# doan20192.net
KiCad netlist of a schematic drawn in EasyEDA
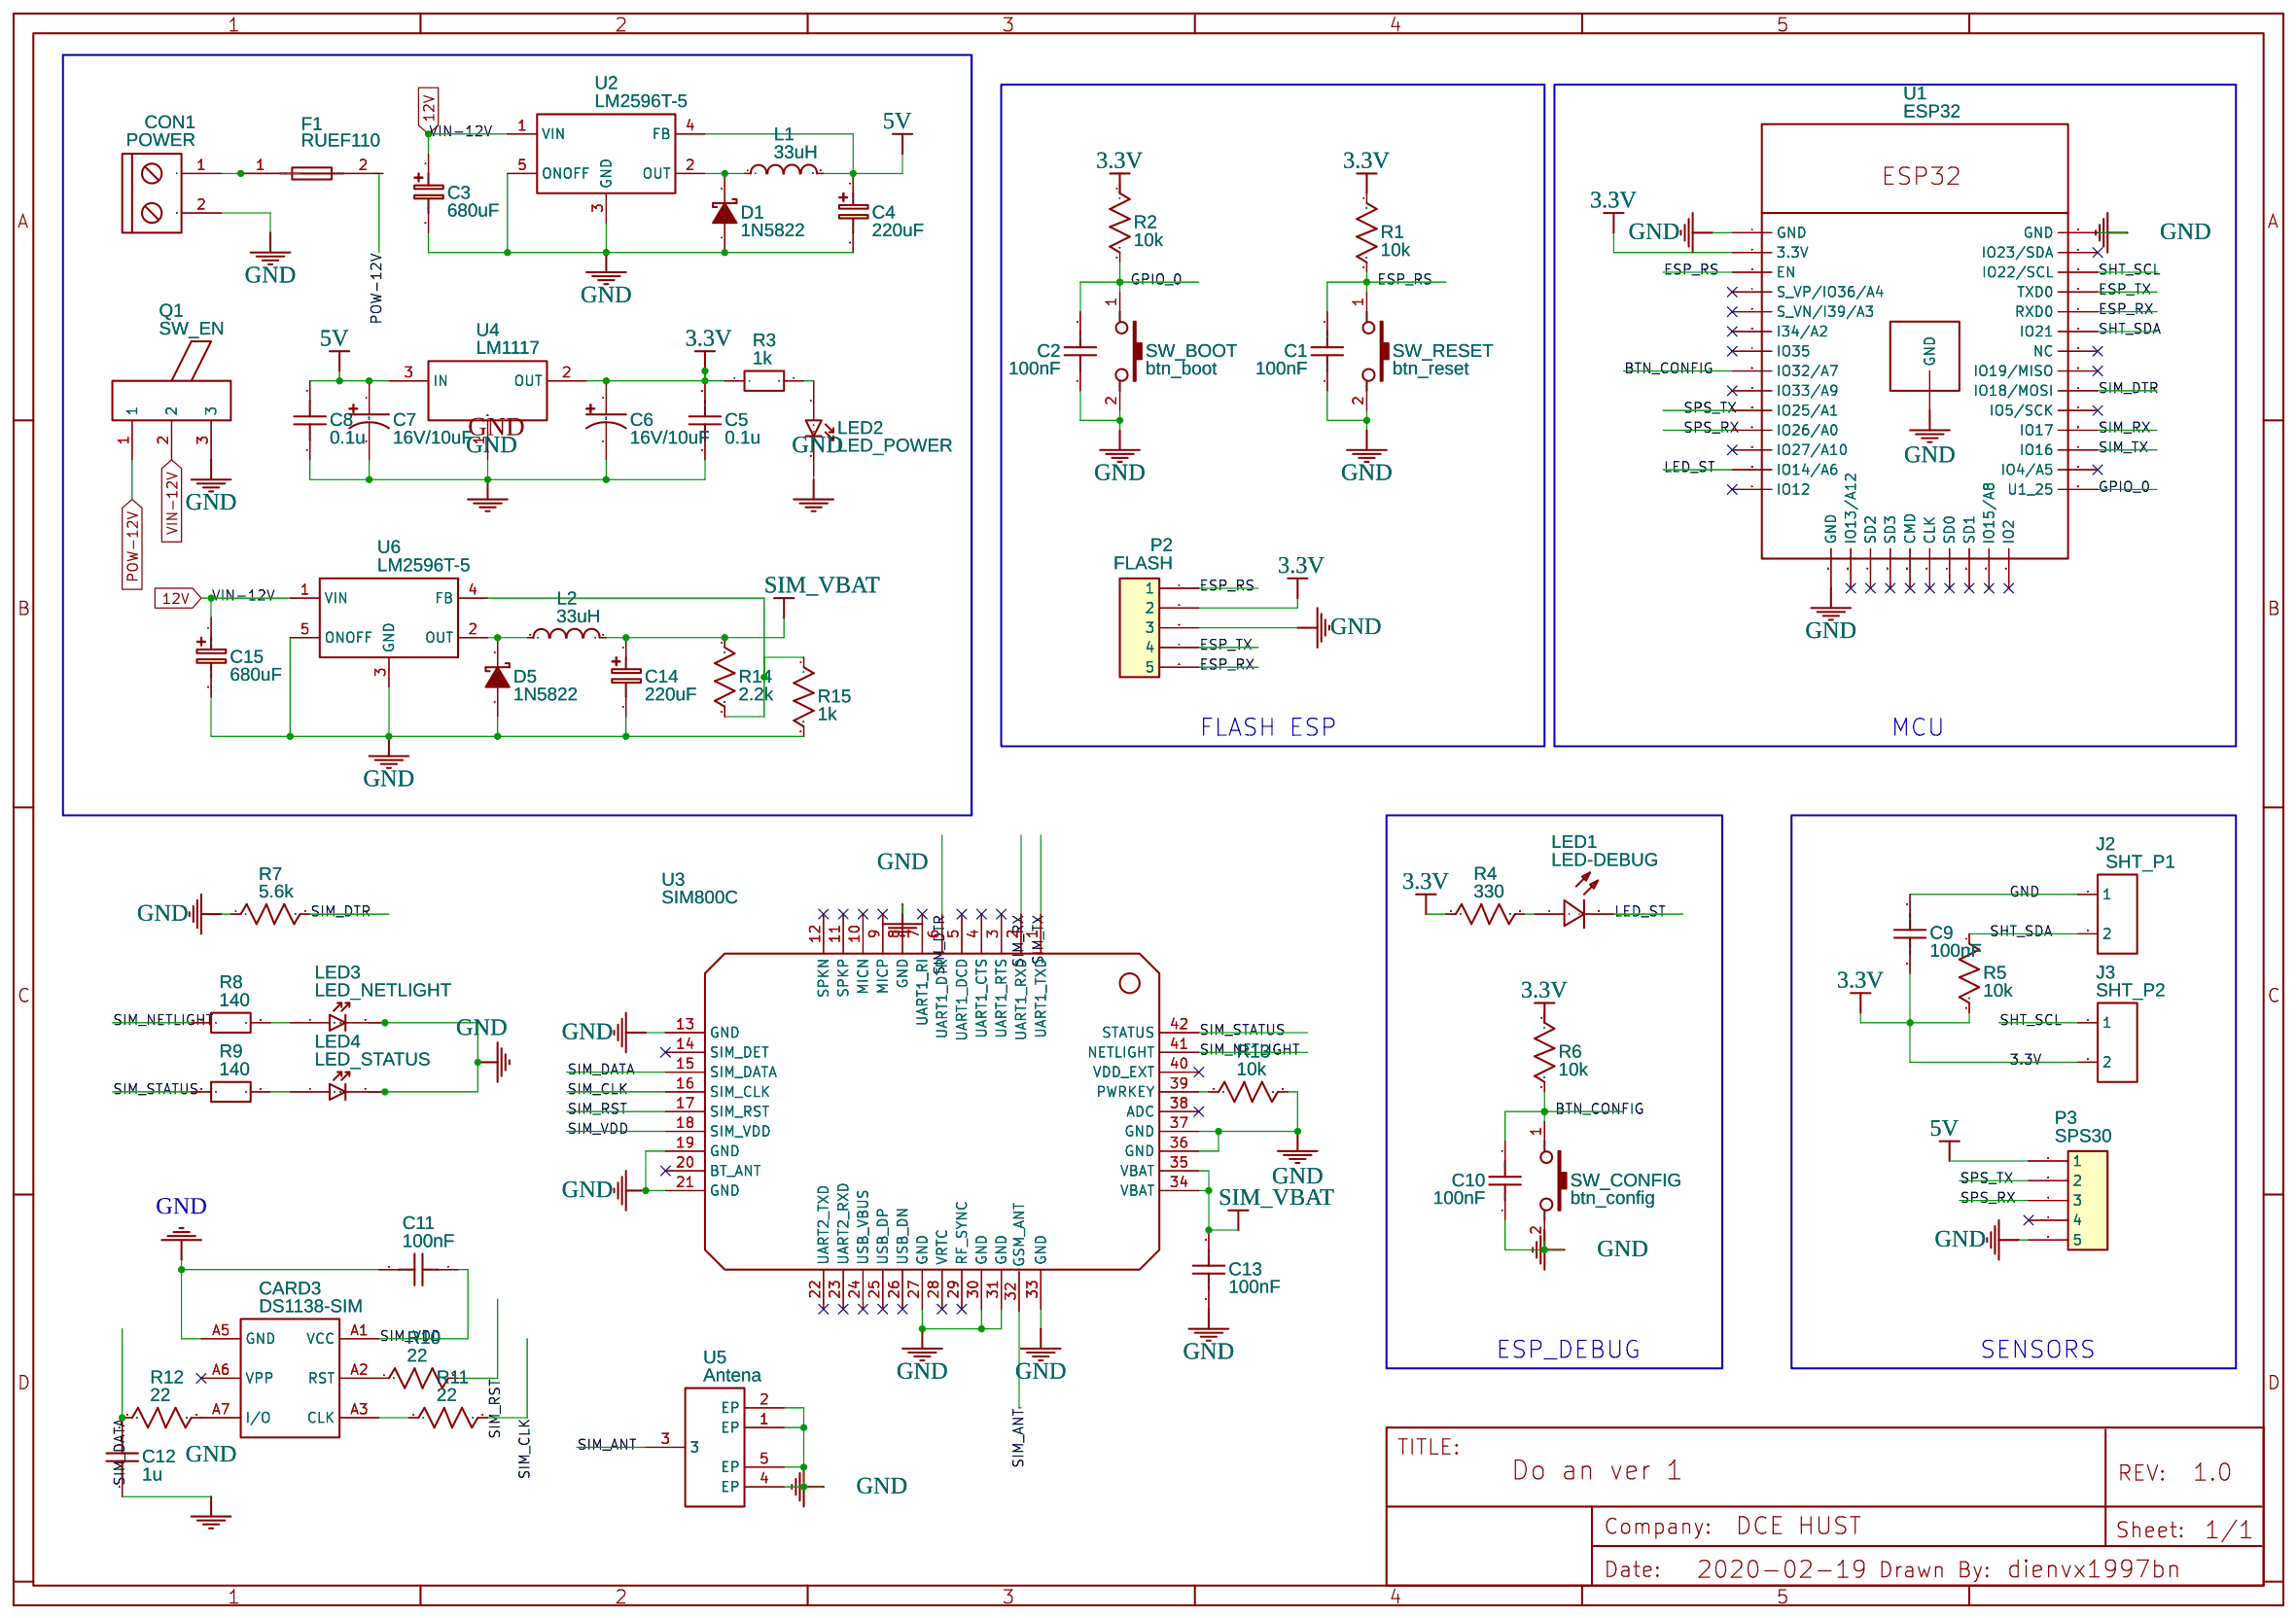
[diagram p0: schematic sheet]

(export (version "E")
  (design (tool "Eeschema 10.0.6"))
  (components
    (comp (ref "C1") (value "100nF") (libsource (lib "") (part "Cap_RAD-0.1_US")))
    (comp (ref "C2") (value "100nF") (libsource (lib "") (part "Cap_RAD-0.1_US")))
    (comp (ref "C3") (value "680uF") (libsource (lib "") (part "Cap_Electrolytic(TH)_D3.0XF1.5_EU_1")))
    (comp (ref "C4") (value "220uF") (libsource (lib "") (part "Cap_Electrolytic(TH)_D3.0XF1.5_EU")))
    (comp (ref "C5") (value "0.1u") (libsource (lib "") (part "Cap_RAD-0.1_US_1")))
    (comp (ref "C6") (value "16V/10uF") (libsource (lib "") (part "Cap_Electrolytic(TH)_D3.0XF1.5_US")))
    (comp (ref "C7") (value "16V/10uF") (libsource (lib "") (part "Cap_Electrolytic(TH)_D3.0XF1.5_US_1")))
    (comp (ref "C8") (value "0.1u") (libsource (lib "") (part "Cap_RAD-0.1_US_1")))
    (comp (ref "C9") (value "100nF") (libsource (lib "") (part "Cap_RAD-0.1_US_1")))
    (comp (ref "C10") (value "100nF") (libsource (lib "") (part "Cap_RAD-0.1_US")))
    (comp (ref "C11") (value "100nF") (libsource (lib "") (part "Cap_RAD-0.1_US_2")))
    (comp (ref "C12") (value "1u") (libsource (lib "") (part "Cap_RAD-0.1_US_1")))
    (comp (ref "C13") (value "100nF") (libsource (lib "") (part "Cap_RAD-0.1_US_1")))
    (comp (ref "C14") (value "220uF") (libsource (lib "") (part "Cap_Electrolytic(TH)_D3.0XF1.5_EU_3")))
    (comp (ref "C15") (value "680uF") (libsource (lib "") (part "Cap_Electrolytic(TH)_D3.0XF1.5_EU_2")))
    (comp (ref "CARD3")
      (value "DS1138-SIM")
      (fields
        (field (name "BOM_Manufacturer Part") "DS1138-06-06SS4BSR")
        (field (name "BOM_Supplier Part") "C96105")
      )
      (libsource (lib "") (part "Unknown_150_-110"))
    )
    (comp (ref "CON1")
      (value "POWER")
      (fields (field (name "BOM_Manufacturer Part") "Connector_2pin"))
      (libsource (lib "") (part "Connector_2pin"))
    )
    (comp (ref "D1")
      (value "1N5822")
      (fields (field (name "BOM_Supplier Part") "C82806"))
      (libsource (lib "") (part "1N5822"))
    )
    (comp (ref "D5")
      (value "1N5822")
      (fields (field (name "BOM_Supplier Part") "C82806"))
      (libsource (lib "") (part "1N5822"))
    )
    (comp (ref "F1")
      (value "RUEF110")
      (fields (field (name "BOM_Supplier Part") "C5395"))
      (libsource (lib "") (part "RUEF110"))
    )
    (comp (ref "J2")
      (value "SHT_P1")
      (fields (field (name "BOM_Manufacturer Part") "826629-2") (field (name "BOM_Supplier Part") "C86471"))
      (libsource (lib "") (part "J-Header-Male-2.54_1x2"))
    )
    (comp (ref "J3")
      (value "SHT_P2")
      (fields (field (name "BOM_Manufacturer Part") "826629-2") (field (name "BOM_Supplier Part") "C86471"))
      (libsource (lib "") (part "J-Header-Male-2.54_1x2"))
    )
    (comp (ref "L1") (value "33uH") (libsource (lib "") (part "Inductor_AXIAL-0.4_US")))
    (comp (ref "L2") (value "33uH") (libsource (lib "") (part "Inductor_AXIAL-0.4_US")))
    (comp (ref "LED1")
      (value "LED-DEBUG")
      (fields
        (field (name "BOM_Manufacturer Part") "204-10SURD/S530-A3")
        (field (name "BOM_Supplier Part") "C99772")
      )
      (libsource (lib "") (part "LED-3MM"))
    )
    (comp (ref "LED2")
      (value "LED_POWER")
      (fields (field (name "BOM_Manufacturer Part") "LED-3MM-RED"))
      (libsource (lib "") (part "LED-3MM-RED"))
    )
    (comp (ref "LED3")
      (value "LED_NETLIGHT")
      (fields (field (name "BOM_Manufacturer Part") "LED-3MM-RED"))
      (libsource (lib "") (part "LED-3MM-RED_1"))
    )
    (comp (ref "LED4")
      (value "LED_STATUS")
      (fields (field (name "BOM_Manufacturer Part") "LED-3MM-RED"))
      (libsource (lib "") (part "LED-3MM-RED_1"))
    )
    (comp (ref "P2")
      (value "FLASH")
      (fields
        (field (name "BOM_Manufacturer Part") "Female header　2.54 1*5Ｐ")
        (field (name "BOM_Supplier Part") "C46341")
      )
      (libsource (lib "") (part "Header-Female-2.54_1x5"))
    )
    (comp (ref "P3")
      (value "SPS30")
      (fields
        (field (name "BOM_Manufacturer Part") "Female header　2.54 1*5Ｐ")
        (field (name "BOM_Supplier Part") "C46341")
      )
      (libsource (lib "") (part "Header-Female-2.54_1x5_1"))
    )
    (comp (ref "Q1")
      (value "SW_EN")
      (fields (field (name "BOM_Manufacturer Part") "MTS-103-A2"))
      (libsource (lib "") (part "MTS-103-A2"))
    )
    (comp (ref "R1") (value "10k") (libsource (lib "") (part "Res_AXIAL-0.3(1/8W)_US")))
    (comp (ref "R2") (value "10k") (libsource (lib "") (part "Res_AXIAL-0.3(1/8W)_US")))
    (comp (ref "R3") (value "1k") (libsource (lib "") (part "Res_AXIAL-0.3(1/8W)_EU")))
    (comp (ref "R4") (value "330") (libsource (lib "") (part "Res_AXIAL-0.3(1/8W)_US_1")))
    (comp (ref "R5") (value "10k") (libsource (lib "") (part "Res_AXIAL-0.3(1/8W)_US")))
    (comp (ref "R6") (value "10k") (libsource (lib "") (part "Res_AXIAL-0.3(1/8W)_US")))
    (comp (ref "R7") (value "5.6k") (libsource (lib "") (part "Res_AXIAL-0.3(1/8W)_US_1")))
    (comp (ref "R8") (value "140") (libsource (lib "") (part "Res_AXIAL-0.3(1/8W)_EU")))
    (comp (ref "R9") (value "140") (libsource (lib "") (part "Res_AXIAL-0.3(1/8W)_EU")))
    (comp (ref "R10") (value "22") (libsource (lib "") (part "Res_AXIAL-0.3(1/8W)_US_1")))
    (comp (ref "R11") (value "22") (libsource (lib "") (part "Res_AXIAL-0.3(1/8W)_US_1")))
    (comp (ref "R12") (value "22") (libsource (lib "") (part "Res_AXIAL-0.3(1/8W)_US_1")))
    (comp (ref "R13") (value "10k") (libsource (lib "") (part "Res_AXIAL-0.3(1/8W)_US_1")))
    (comp (ref "R14") (value "2.2k") (libsource (lib "") (part "Res_AXIAL-0.3(1/8W)_US")))
    (comp (ref "R15") (value "1k") (libsource (lib "") (part "Res_AXIAL-0.3(1/8W)_US")))
    (comp (ref "SW_BOOT")
      (value "btn_boot")
      (fields
        (field (name "BOM_Manufacturer Part") "Switch,6*6*6Plastic head,260G, 0.25mm,Straight line")
        (field (name "BOM_Supplier Part") "C71836")
      )
      (libsource (lib "") (part "Button-6x6x6mm"))
    )
    (comp (ref "SW_CONFIG")
      (value "btn_config")
      (fields
        (field (name "BOM_Manufacturer Part") "Switch,6*6*6Plastic head,260G, 0.25mm,Straight line")
        (field (name "BOM_Supplier Part") "C71836")
      )
      (libsource (lib "") (part "Button-6x6x6mm_2"))
    )
    (comp (ref "SW_RESET")
      (value "btn_reset")
      (fields
        (field (name "BOM_Manufacturer Part") "Switch,6*6*6Plastic head,260G, 0.25mm,Straight line")
        (field (name "BOM_Supplier Part") "C71836")
      )
      (libsource (lib "") (part "Button-6x6x6mm_1"))
    )
    (comp (ref "U1")
      (value "ESP32")
      (fields (field (name "BOM_Manufacturer Part") "New SchematicLib"))
      (libsource (lib "") (part "ESP32"))
    )
    (comp (ref "U2")
      (value "LM2596T-5")
      (fields (field (name "BOM_Supplier Part") "undefined"))
      (libsource (lib "") (part "LM2596T-5"))
    )
    (comp (ref "U3")
      (value "SIM800C")
      (fields
        (field (name "BOM_Manufacturer Part") "SIM800C 24Mbit")
        (field (name "BOM_Supplier Part") "C69119")
      )
      (libsource (lib "") (part "SIM800C"))
    )
    (comp (ref "U4") (value "LM1117") (libsource (lib "") (part "LM1117T-5.0NOPB")))
    (comp (ref "U5")
      (value "Antena")
      (fields
        (field (name "BOM_Manufacturer Part") "5-1814832-1")
        (field (name "BOM_Supplier Part") "C127838")
      )
      (libsource (lib "") (part "Unknown_360_-85"))
    )
    (comp (ref "U6")
      (value "LM2596T-5")
      (fields (field (name "BOM_Supplier Part") "undefined"))
      (libsource (lib "") (part "LM2596T-5"))
    )
  )
  (nets
    (net (code "1") (name "/BTN_CONFIG") (class "Default")
      (node (ref "C10") (pin "2") (pinfunction "2_2") (pintype "unspecified"))
      (node (ref "R6") (pin "2") (pinfunction "2_2") (pintype "unspecified"))
      (node (ref "SW_CONFIG") (pin "1") (pinfunction "1_1") (pintype "input"))
      (node (ref "U1") (pin "8") (pinfunction "IO32/A7_8") (pintype "unspecified"))
    )
    (net (code "2") (name "/ESP_RS") (class "Default")
      (node (ref "C1") (pin "2") (pinfunction "2_2") (pintype "unspecified"))
      (node (ref "P2") (pin "1") (pinfunction "1_1") (pintype "input"))
      (node (ref "R1") (pin "2") (pinfunction "2_2") (pintype "unspecified"))
      (node (ref "SW_RESET") (pin "1") (pinfunction "1_1") (pintype "input"))
      (node (ref "U1") (pin "3") (pinfunction "EN_3") (pintype "unspecified"))
    )
    (net (code "3") (name "/ESP_RX") (class "Default")
      (node (ref "P2") (pin "5") (pinfunction "5_5") (pintype "input"))
      (node (ref "U1") (pin "34") (pinfunction "RXD0_34") (pintype "unspecified"))
    )
    (net (code "4") (name "/ESP_TX") (class "Default")
      (node (ref "P2") (pin "4") (pinfunction "4_4") (pintype "input"))
      (node (ref "U1") (pin "35") (pinfunction "TXD0_35") (pintype "unspecified"))
    )
    (net (code "5") (name "/GPIO_0") (class "Default")
      (node (ref "C2") (pin "2") (pinfunction "2_2") (pintype "unspecified"))
      (node (ref "R2") (pin "2") (pinfunction "2_2") (pintype "unspecified"))
      (node (ref "SW_BOOT") (pin "1") (pinfunction "1_1") (pintype "input"))
      (node (ref "U1") (pin "25") (pinfunction "U1_25_25") (pintype "unspecified"))
    )
    (net (code "6") (name "/LED_ST") (class "Default")
      (node (ref "LED1") (pin "2") (pinfunction "-_2") (pintype "unspecified"))
      (node (ref "U1") (pin "13") (pinfunction "IO14/A6_13") (pintype "unspecified"))
    )
    (net (code "7") (name "/SHT_SCL") (class "Default")
      (node (ref "J3") (pin "1") (pinfunction "1_1") (pintype "unspecified"))
      (node (ref "U1") (pin "36") (pinfunction "IO22/SCL_36") (pintype "unspecified"))
    )
    (net (code "8") (name "/SHT_SDA") (class "Default")
      (node (ref "J2") (pin "2") (pinfunction "2_2") (pintype "unspecified"))
      (node (ref "R5") (pin "1") (pinfunction "1_1") (pintype "unspecified"))
      (node (ref "U1") (pin "33") (pinfunction "IO21_33") (pintype "unspecified"))
    )
    (net (code "9") (name "/SIM_ANT") (class "Default")
      (node (ref "U3") (pin "32") (pinfunction "GSM_ANT_32") (pintype "unspecified"))
      (node (ref "U5") (pin "3") (pinfunction "3_3") (pintype "unspecified"))
    )
    (net (code "10") (name "/SIM_CLK") (class "Default")
      (node (ref "R11") (pin "2") (pinfunction "2_2") (pintype "unspecified"))
      (node (ref "U3") (pin "16") (pinfunction "SIM_CLK_16") (pintype "unspecified"))
    )
    (net (code "11") (name "/SIM_DATA") (class "Default")
      (node (ref "C12") (pin "2") (pinfunction "2_2") (pintype "unspecified"))
      (node (ref "R12") (pin "1") (pinfunction "1_1") (pintype "unspecified"))
      (node (ref "U3") (pin "15") (pinfunction "SIM_DATA_15") (pintype "unspecified"))
    )
    (net (code "12") (name "/SIM_DTR") (class "Default")
      (node (ref "R7") (pin "2") (pinfunction "2_2") (pintype "unspecified"))
      (node (ref "U1") (pin "30") (pinfunction "IO18/MOSI_30") (pintype "unspecified"))
      (node (ref "U3") (pin "6") (pinfunction "UART1_DTR_6") (pintype "unspecified"))
    )
    (net (code "13") (name "/SIM_NETLIGHT") (class "Default")
      (node (ref "R8") (pin "1") (pinfunction "1_1") (pintype "unspecified"))
      (node (ref "U3") (pin "41") (pinfunction "NETLIGHT_41") (pintype "unspecified"))
    )
    (net (code "14") (name "/SIM_RST") (class "Default")
      (node (ref "R10") (pin "2") (pinfunction "2_2") (pintype "unspecified"))
      (node (ref "U3") (pin "17") (pinfunction "SIM_RST_17") (pintype "unspecified"))
    )
    (net (code "15") (name "/SIM_RX") (class "Default")
      (node (ref "U1") (pin "28") (pinfunction "IO17_28") (pintype "unspecified"))
      (node (ref "U3") (pin "2") (pinfunction "UART1_RXD_2") (pintype "unspecified"))
    )
    (net (code "16") (name "/SIM_STATUS") (class "Default")
      (node (ref "R9") (pin "1") (pinfunction "1_1") (pintype "unspecified"))
      (node (ref "U3") (pin "42") (pinfunction "STATUS_42") (pintype "unspecified"))
    )
    (net (code "17") (name "/SIM_TX") (class "Default")
      (node (ref "U1") (pin "27") (pinfunction "IO16_27") (pintype "unspecified"))
      (node (ref "U3") (pin "1") (pinfunction "UART1_TXD_1") (pintype "unspecified"))
    )
    (net (code "18") (name "/SIM_VDD") (class "Default")
      (node (ref "C11") (pin "1") (pinfunction "1_1") (pintype "unspecified"))
      (node (ref "CARD3") (pin "A1") (pinfunction "VCC_A1") (pintype "unspecified"))
      (node (ref "U3") (pin "18") (pinfunction "SIM_VDD_18") (pintype "unspecified"))
    )
    (net (code "19") (name "/SPS_RX") (class "Default")
      (node (ref "P3") (pin "3") (pinfunction "3_3") (pintype "input"))
      (node (ref "U1") (pin "11") (pinfunction "IO26/A0_11") (pintype "unspecified"))
    )
    (net (code "20") (name "/SPS_TX") (class "Default")
      (node (ref "P3") (pin "2") (pinfunction "2_2") (pintype "input"))
      (node (ref "U1") (pin "10") (pinfunction "IO25/A1_10") (pintype "unspecified"))
    )
    (net (code "21") (name "3.3V") (class "Default")
      (node (ref "C5") (pin "2") (pinfunction "2_2") (pintype "unspecified"))
      (node (ref "C6") (pin "1") (pinfunction "1_1") (pintype "unspecified"))
      (node (ref "C9") (pin "1") (pinfunction "1_1") (pintype "unspecified"))
      (node (ref "J3") (pin "2") (pinfunction "2_2") (pintype "unspecified"))
      (node (ref "P2") (pin "2") (pinfunction "2_2") (pintype "input"))
      (node (ref "R1") (pin "1") (pinfunction "1_1") (pintype "unspecified"))
      (node (ref "R2") (pin "1") (pinfunction "1_1") (pintype "unspecified"))
      (node (ref "R3") (pin "1") (pinfunction "1_1") (pintype "unspecified"))
      (node (ref "R4") (pin "1") (pinfunction "1_1") (pintype "unspecified"))
      (node (ref "R5") (pin "2") (pinfunction "2_2") (pintype "unspecified"))
      (node (ref "R6") (pin "1") (pinfunction "1_1") (pintype "unspecified"))
      (node (ref "U1") (pin "2") (pinfunction "3.3V_2") (pintype "unspecified"))
      (node (ref "U4") (pin "2") (pinfunction "OUT_2") (pintype "passive"))
    )
    (net (code "22") (name "5V") (class "Default")
      (node (ref "C4") (pin "1") (pinfunction "1_1") (pintype "unspecified"))
      (node (ref "C7") (pin "1") (pinfunction "1_1") (pintype "unspecified"))
      (node (ref "C8") (pin "2") (pinfunction "2_2") (pintype "unspecified"))
      (node (ref "L1") (pin "2") (pinfunction "2_2") (pintype "unspecified"))
      (node (ref "P3") (pin "1") (pinfunction "1_1") (pintype "input"))
      (node (ref "U2") (pin "4") (pinfunction "FB_4") (pintype "input"))
      (node (ref "U4") (pin "3") (pinfunction "IN_3") (pintype "passive"))
    )
    (net (code "23") (name "12V") (class "Default")
      (node (ref "C15") (pin "1") (pinfunction "1_1") (pintype "unspecified"))
      (node (ref "C3") (pin "1") (pinfunction "1_1") (pintype "unspecified"))
      (node (ref "Q1") (pin "2") (pinfunction "2_2") (pintype "unspecified"))
      (node (ref "U2") (pin "1") (pinfunction "VIN_1") (pintype "passive"))
      (node (ref "U6") (pin "1") (pinfunction "VIN_1") (pintype "passive"))
    )
    (net (code "24") (name "GND") (class "Default")
      (node (ref "C1") (pin "1") (pinfunction "1_1") (pintype "unspecified"))
      (node (ref "C10") (pin "1") (pinfunction "1_1") (pintype "unspecified"))
      (node (ref "C11") (pin "2") (pinfunction "2_2") (pintype "unspecified"))
      (node (ref "C12") (pin "1") (pinfunction "1_1") (pintype "unspecified"))
      (node (ref "C13") (pin "1") (pinfunction "1_1") (pintype "unspecified"))
      (node (ref "C14") (pin "2") (pinfunction "2_2") (pintype "unspecified"))
      (node (ref "C15") (pin "2") (pinfunction "2_2") (pintype "unspecified"))
      (node (ref "C2") (pin "1") (pinfunction "1_1") (pintype "unspecified"))
      (node (ref "C3") (pin "2") (pinfunction "2_2") (pintype "unspecified"))
      (node (ref "C4") (pin "2") (pinfunction "2_2") (pintype "unspecified"))
      (node (ref "C5") (pin "1") (pinfunction "1_1") (pintype "unspecified"))
      (node (ref "C6") (pin "2") (pinfunction "2_2") (pintype "unspecified"))
      (node (ref "C7") (pin "2") (pinfunction "2_2") (pintype "unspecified"))
      (node (ref "C8") (pin "1") (pinfunction "1_1") (pintype "unspecified"))
      (node (ref "C9") (pin "2") (pinfunction "2_2") (pintype "unspecified"))
      (node (ref "CARD3") (pin "A5") (pinfunction "GND_A5") (pintype "unspecified"))
      (node (ref "CON1") (pin "2") (pinfunction "2_2") (pintype "unspecified"))
      (node (ref "D1") (pin "1") (pinfunction "A_1") (pintype "unspecified"))
      (node (ref "D5") (pin "1") (pinfunction "A_1") (pintype "unspecified"))
      (node (ref "J2") (pin "1") (pinfunction "1_1") (pintype "unspecified"))
      (node (ref "LED2") (pin "2") (pinfunction "2_2") (pintype "unspecified"))
      (node (ref "LED3") (pin "2") (pinfunction "2_2") (pintype "unspecified"))
      (node (ref "LED4") (pin "2") (pinfunction "2_2") (pintype "unspecified"))
      (node (ref "P2") (pin "3") (pinfunction "3_3") (pintype "input"))
      (node (ref "P3") (pin "5") (pinfunction "5_5") (pintype "input"))
      (node (ref "Q1") (pin "3") (pinfunction "3_3") (pintype "unspecified"))
      (node (ref "R13") (pin "2") (pinfunction "2_2") (pintype "unspecified"))
      (node (ref "R15") (pin "2") (pinfunction "2_2") (pintype "unspecified"))
      (node (ref "R7") (pin "1") (pinfunction "1_1") (pintype "unspecified"))
      (node (ref "SW_BOOT") (pin "2") (pinfunction "2_2") (pintype "input"))
      (node (ref "SW_CONFIG") (pin "2") (pinfunction "2_2") (pintype "input"))
      (node (ref "SW_RESET") (pin "2") (pinfunction "2_2") (pintype "input"))
      (node (ref "U1") (pin "1") (pinfunction "GND_1") (pintype "unspecified"))
      (node (ref "U1") (pin "15") (pinfunction "GND_15") (pintype "unspecified"))
      (node (ref "U1") (pin "38") (pinfunction "GND_38") (pintype "unspecified"))
      (node (ref "U1") (pin "39") (pinfunction "GND_39") (pintype "unspecified"))
      (node (ref "U2") (pin "3") (pinfunction "GND_3") (pintype "passive"))
      (node (ref "U2") (pin "5") (pinfunction "ONOFF_5") (pintype "input"))
      (node (ref "U3") (pin "13") (pinfunction "GND_13") (pintype "unspecified"))
      (node (ref "U3") (pin "19") (pinfunction "GND_19") (pintype "unspecified"))
      (node (ref "U3") (pin "21") (pinfunction "GND_21") (pintype "unspecified"))
      (node (ref "U3") (pin "27") (pinfunction "GND_27") (pintype "unspecified"))
      (node (ref "U3") (pin "30") (pinfunction "GND_30") (pintype "unspecified"))
      (node (ref "U3") (pin "31") (pinfunction "GND_31") (pintype "unspecified"))
      (node (ref "U3") (pin "33") (pinfunction "GND_33") (pintype "unspecified"))
      (node (ref "U3") (pin "36") (pinfunction "GND_36") (pintype "unspecified"))
      (node (ref "U3") (pin "37") (pinfunction "GND_37") (pintype "unspecified"))
      (node (ref "U3") (pin "8") (pinfunction "GND_8") (pintype "unspecified"))
      (node (ref "U4") (pin "1") (pinfunction "GND_1") (pintype "passive"))
      (node (ref "U5") (pin "1") (pinfunction "EP_1") (pintype "unspecified"))
      (node (ref "U5") (pin "2") (pinfunction "EP_2") (pintype "unspecified"))
      (node (ref "U5") (pin "4") (pinfunction "EP_4") (pintype "unspecified"))
      (node (ref "U5") (pin "5") (pinfunction "EP_5") (pintype "unspecified"))
      (node (ref "U6") (pin "3") (pinfunction "GND_3") (pintype "passive"))
      (node (ref "U6") (pin "5") (pinfunction "ONOFF_5") (pintype "input"))
    )
    (net (code "25") (name "Net-(CARD3-CLK)") (class "Default")
      (node (ref "CARD3") (pin "A3") (pinfunction "CLK_A3") (pintype "unspecified"))
      (node (ref "R11") (pin "1") (pinfunction "1_1") (pintype "unspecified"))
    )
    (net (code "26") (name "Net-(CARD3-I{slash}O)") (class "Default")
      (node (ref "CARD3") (pin "A7") (pinfunction "I/O_A7") (pintype "unspecified"))
      (node (ref "R12") (pin "2") (pinfunction "2_2") (pintype "unspecified"))
    )
    (net (code "27") (name "Net-(CARD3-RST)") (class "Default")
      (node (ref "CARD3") (pin "A2") (pinfunction "RST_A2") (pintype "unspecified"))
      (node (ref "R10") (pin "1") (pinfunction "1_1") (pintype "unspecified"))
    )
    (net (code "28") (name "Net-(CON1-Pad1)") (class "Default")
      (node (ref "CON1") (pin "1") (pinfunction "1_1") (pintype "unspecified"))
      (node (ref "F1") (pin "1") (pinfunction "1_1") (pintype "unspecified"))
    )
    (net (code "29") (name "Net-(D1-K)") (class "Default")
      (node (ref "D1") (pin "2") (pinfunction "K_2") (pintype "unspecified"))
      (node (ref "L1") (pin "1") (pinfunction "1_1") (pintype "unspecified"))
      (node (ref "U2") (pin "2") (pinfunction "OUT_2") (pintype "output"))
    )
    (net (code "30") (name "Net-(D5-K)") (class "Default")
      (node (ref "D5") (pin "2") (pinfunction "K_2") (pintype "unspecified"))
      (node (ref "L2") (pin "1") (pinfunction "1_1") (pintype "unspecified"))
      (node (ref "U6") (pin "2") (pinfunction "OUT_2") (pintype "output"))
    )
    (net (code "31") (name "Net-(LED1-+)") (class "Default")
      (node (ref "LED1") (pin "1") (pinfunction "+_1") (pintype "unspecified"))
      (node (ref "R4") (pin "2") (pinfunction "2_2") (pintype "unspecified"))
    )
    (net (code "32") (name "Net-(LED2-Pad1)") (class "Default")
      (node (ref "LED2") (pin "1") (pinfunction "1_1") (pintype "unspecified"))
      (node (ref "R3") (pin "2") (pinfunction "2_2") (pintype "unspecified"))
    )
    (net (code "33") (name "Net-(LED3-Pad1)") (class "Default")
      (node (ref "LED3") (pin "1") (pinfunction "1_1") (pintype "unspecified"))
      (node (ref "R8") (pin "2") (pinfunction "2_2") (pintype "unspecified"))
    )
    (net (code "34") (name "Net-(LED4-Pad1)") (class "Default")
      (node (ref "LED4") (pin "1") (pinfunction "1_1") (pintype "unspecified"))
      (node (ref "R9") (pin "2") (pinfunction "2_2") (pintype "unspecified"))
    )
    (net (code "35") (name "Net-(U3-PWRKEY)") (class "Default")
      (node (ref "R13") (pin "1") (pinfunction "1_1") (pintype "unspecified"))
      (node (ref "U3") (pin "39") (pinfunction "PWRKEY_39") (pintype "unspecified"))
    )
    (net (code "36") (name "Net-(U6-FB)") (class "Default")
      (node (ref "R14") (pin "2") (pinfunction "2_2") (pintype "unspecified"))
      (node (ref "R15") (pin "1") (pinfunction "1_1") (pintype "unspecified"))
      (node (ref "U6") (pin "4") (pinfunction "FB_4") (pintype "input"))
    )
    (net (code "37") (name "POW-12V") (class "Default")
      (node (ref "Q1") (pin "1") (pinfunction "1_1") (pintype "unspecified"))
    )
    (net (code "38") (name "SIM_VBAT") (class "Default")
      (node (ref "C13") (pin "2") (pinfunction "2_2") (pintype "unspecified"))
      (node (ref "C14") (pin "1") (pinfunction "1_1") (pintype "unspecified"))
      (node (ref "L2") (pin "2") (pinfunction "2_2") (pintype "unspecified"))
      (node (ref "R14") (pin "1") (pinfunction "1_1") (pintype "unspecified"))
      (node (ref "U3") (pin "34") (pinfunction "VBAT_34") (pintype "unspecified"))
      (node (ref "U3") (pin "35") (pinfunction "VBAT_35") (pintype "unspecified"))
    )
    (net (code "39") (name "unconnected-(CARD3-VPP-PadA6)") (class "Default")
      (node (ref "CARD3") (pin "A6") (pinfunction "VPP_A6") (pintype "unspecified+no_connect"))
    )
    (net (code "40") (name "unconnected-(F1-Pad2)") (class "Default")
      (node (ref "F1") (pin "2") (pinfunction "2_2") (pintype "unspecified"))
    )
    (net (code "41") (name "unconnected-(P3-Pad4)") (class "Default")
      (node (ref "P3") (pin "4") (pinfunction "4_4") (pintype "input+no_connect"))
    )
    (net (code "42") (name "unconnected-(U1-CLK-Pad20)") (class "Default")
      (node (ref "U1") (pin "20") (pinfunction "CLK_20") (pintype "unspecified+no_connect"))
    )
    (net (code "43") (name "unconnected-(U1-CMD-Pad19)") (class "Default")
      (node (ref "U1") (pin "19") (pinfunction "CMD_19") (pintype "unspecified+no_connect"))
    )
    (net (code "44") (name "unconnected-(U1-I34{slash}A2-Pad6)") (class "Default")
      (node (ref "U1") (pin "6") (pinfunction "I34/A2_6") (pintype "unspecified+no_connect"))
    )
    (net (code "45") (name "unconnected-(U1-IO2-Pad24)") (class "Default")
      (node (ref "U1") (pin "24") (pinfunction "IO2_24") (pintype "unspecified+no_connect"))
    )
    (net (code "46") (name "unconnected-(U1-IO4{slash}A5-Pad26)") (class "Default")
      (node (ref "U1") (pin "26") (pinfunction "IO4/A5_26") (pintype "unspecified+no_connect"))
    )
    (net (code "47") (name "unconnected-(U1-IO5{slash}SCK-Pad29)") (class "Default")
      (node (ref "U1") (pin "29") (pinfunction "IO5/SCK_29") (pintype "unspecified+no_connect"))
    )
    (net (code "48") (name "unconnected-(U1-IO12-Pad14)") (class "Default")
      (node (ref "U1") (pin "14") (pinfunction "IO12_14") (pintype "unspecified+no_connect"))
    )
    (net (code "49") (name "unconnected-(U1-IO13{slash}A12-Pad16)") (class "Default")
      (node (ref "U1") (pin "16") (pinfunction "IO13/A12_16") (pintype "unspecified+no_connect"))
    )
    (net (code "50") (name "unconnected-(U1-IO15{slash}A8-Pad23)") (class "Default")
      (node (ref "U1") (pin "23") (pinfunction "IO15/A8_23") (pintype "unspecified+no_connect"))
    )
    (net (code "51") (name "unconnected-(U1-IO19{slash}MISO-Pad31)") (class "Default")
      (node (ref "U1") (pin "31") (pinfunction "IO19/MISO_31") (pintype "unspecified+no_connect"))
    )
    (net (code "52") (name "unconnected-(U1-IO23{slash}SDA-Pad37)") (class "Default")
      (node (ref "U1") (pin "37") (pinfunction "IO23/SDA_37") (pintype "unspecified+no_connect"))
    )
    (net (code "53") (name "unconnected-(U1-IO27{slash}A10-Pad12)") (class "Default")
      (node (ref "U1") (pin "12") (pinfunction "IO27/A10_12") (pintype "unspecified+no_connect"))
    )
    (net (code "54") (name "unconnected-(U1-IO33{slash}A9-Pad9)") (class "Default")
      (node (ref "U1") (pin "9") (pinfunction "IO33/A9_9") (pintype "unspecified+no_connect"))
    )
    (net (code "55") (name "unconnected-(U1-IO35-Pad7)") (class "Default")
      (node (ref "U1") (pin "7") (pinfunction "IO35_7") (pintype "unspecified+no_connect"))
    )
    (net (code "56") (name "unconnected-(U1-NC-Pad32)") (class "Default")
      (node (ref "U1") (pin "32") (pinfunction "NC_32") (pintype "unspecified+no_connect"))
    )
    (net (code "57") (name "unconnected-(U1-SD0-Pad21)") (class "Default")
      (node (ref "U1") (pin "21") (pinfunction "SD0_21") (pintype "unspecified+no_connect"))
    )
    (net (code "58") (name "unconnected-(U1-SD1-Pad22)") (class "Default")
      (node (ref "U1") (pin "22") (pinfunction "SD1_22") (pintype "unspecified+no_connect"))
    )
    (net (code "59") (name "unconnected-(U1-SD2-Pad17)") (class "Default")
      (node (ref "U1") (pin "17") (pinfunction "SD2_17") (pintype "unspecified+no_connect"))
    )
    (net (code "60") (name "unconnected-(U1-SD3-Pad18)") (class "Default")
      (node (ref "U1") (pin "18") (pinfunction "SD3_18") (pintype "unspecified+no_connect"))
    )
    (net (code "61") (name "unconnected-(U1-S_VN{slash}I39{slash}A3-Pad5)") (class "Default")
      (node (ref "U1") (pin "5") (pinfunction "S_VN/I39/A3_5") (pintype "unspecified+no_connect"))
    )
    (net (code "62") (name "unconnected-(U1-S_VP{slash}IO36{slash}A4-Pad4)") (class "Default")
      (node (ref "U1") (pin "4") (pinfunction "S_VP/IO36/A4_4") (pintype "unspecified+no_connect"))
    )
    (net (code "63") (name "unconnected-(U3-ADC-Pad38)") (class "Default")
      (node (ref "U3") (pin "38") (pinfunction "ADC_38") (pintype "unspecified+no_connect"))
    )
    (net (code "64") (name "unconnected-(U3-BT_ANT-Pad20)") (class "Default")
      (node (ref "U3") (pin "20") (pinfunction "BT_ANT_20") (pintype "unspecified+no_connect"))
    )
    (net (code "65") (name "unconnected-(U3-MICN-Pad10)") (class "Default")
      (node (ref "U3") (pin "10") (pinfunction "MICN_10") (pintype "unspecified+no_connect"))
    )
    (net (code "66") (name "unconnected-(U3-MICP-Pad9)") (class "Default")
      (node (ref "U3") (pin "9") (pinfunction "MICP_9") (pintype "unspecified+no_connect"))
    )
    (net (code "67") (name "unconnected-(U3-RF_SYNC-Pad29)") (class "Default")
      (node (ref "U3") (pin "29") (pinfunction "RF_SYNC_29") (pintype "unspecified+no_connect"))
    )
    (net (code "68") (name "unconnected-(U3-SIM_DET-Pad14)") (class "Default")
      (node (ref "U3") (pin "14") (pinfunction "SIM_DET_14") (pintype "unspecified+no_connect"))
    )
    (net (code "69") (name "unconnected-(U3-SPKN-Pad12)") (class "Default")
      (node (ref "U3") (pin "12") (pinfunction "SPKN_12") (pintype "unspecified+no_connect"))
    )
    (net (code "70") (name "unconnected-(U3-SPKP-Pad11)") (class "Default")
      (node (ref "U3") (pin "11") (pinfunction "SPKP_11") (pintype "unspecified+no_connect"))
    )
    (net (code "71") (name "unconnected-(U3-UART1_CTS-Pad4)") (class "Default")
      (node (ref "U3") (pin "4") (pinfunction "UART1_CTS_4") (pintype "unspecified+no_connect"))
    )
    (net (code "72") (name "unconnected-(U3-UART1_DCD-Pad5)") (class "Default")
      (node (ref "U3") (pin "5") (pinfunction "UART1_DCD_5") (pintype "unspecified+no_connect"))
    )
    (net (code "73") (name "unconnected-(U3-UART1_RI-Pad7)") (class "Default")
      (node (ref "U3") (pin "7") (pinfunction "UART1_RI_7") (pintype "unspecified+no_connect"))
    )
    (net (code "74") (name "unconnected-(U3-UART1_RTS-Pad3)") (class "Default")
      (node (ref "U3") (pin "3") (pinfunction "UART1_RTS_3") (pintype "unspecified+no_connect"))
    )
    (net (code "75") (name "unconnected-(U3-UART2_RXD-Pad23)") (class "Default")
      (node (ref "U3") (pin "23") (pinfunction "UART2_RXD_23") (pintype "unspecified+no_connect"))
    )
    (net (code "76") (name "unconnected-(U3-UART2_TXD-Pad22)") (class "Default")
      (node (ref "U3") (pin "22") (pinfunction "UART2_TXD_22") (pintype "unspecified+no_connect"))
    )
    (net (code "77") (name "unconnected-(U3-USB_DN-Pad26)") (class "Default")
      (node (ref "U3") (pin "26") (pinfunction "USB_DN_26") (pintype "unspecified+no_connect"))
    )
    (net (code "78") (name "unconnected-(U3-USB_DP-Pad25)") (class "Default")
      (node (ref "U3") (pin "25") (pinfunction "USB_DP_25") (pintype "unspecified+no_connect"))
    )
    (net (code "79") (name "unconnected-(U3-USB_VBUS-Pad24)") (class "Default")
      (node (ref "U3") (pin "24") (pinfunction "USB_VBUS_24") (pintype "unspecified+no_connect"))
    )
    (net (code "80") (name "unconnected-(U3-VDD_EXT-Pad40)") (class "Default")
      (node (ref "U3") (pin "40") (pinfunction "VDD_EXT_40") (pintype "unspecified+no_connect"))
    )
    (net (code "81") (name "unconnected-(U3-VRTC-Pad28)") (class "Default")
      (node (ref "U3") (pin "28") (pinfunction "VRTC_28") (pintype "unspecified+no_connect"))
    )
  )
)
